# ZenDriver_Mini2.net
KiCad netlist of a schematic drawn in Altium Designer
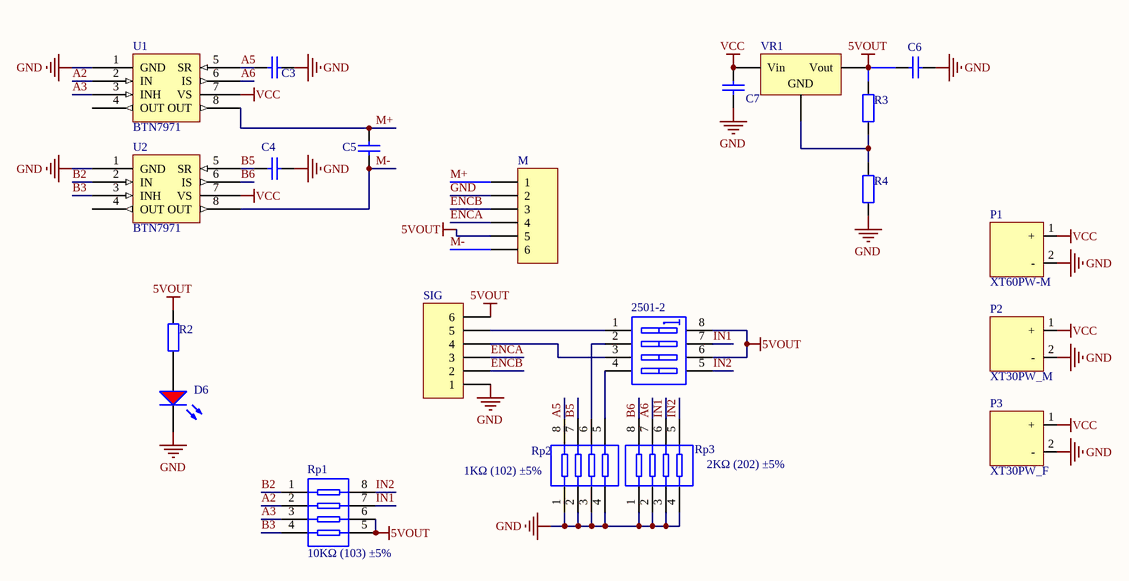
[diagram p0: ZenDriver_Mini2.SchDoc]

(export (version "E")
  (design (tool "Eeschema 10.0.6"))
  (components
    (comp (ref "2501-2")
      (value "2501-2")
      (footprint "*DIP762W50P254L977H451Q8")
      (description "DIP Switch, 4 Position, SPST")
      (fields (field (name "PUBLISHER") "Altium Limited"))
      (libsource (lib "Miscellaneous Devices") (part "SW DIP-4"))
    )
    (comp (ref "C3")
      (value "100nF (104) 10% 50V")
      (footprint "0603_C")
      (description "贴片电容")
      (libsource (lib "Miscellaneous Devices LC") (part "0603 100nF (104) 10% 50V"))
    )
    (comp (ref "C4")
      (value "100nF (104) 10% 50V")
      (footprint "0603_C")
      (description "贴片电容")
      (libsource (lib "Miscellaneous Devices LC") (part "0603 100nF (104) 10% 50V"))
    )
    (comp (ref "C5")
      (value "22pF (220) 5% 50V")
      (footprint "0603_C")
      (description "贴片电容")
      (libsource (lib "Miscellaneous Devices LC") (part "0603 22pF (220) 5% 50V"))
    )
    (comp (ref "C6")
      (value "100nF (104) 10% 50V")
      (footprint "0603_C")
      (description "贴片电容")
      (libsource (lib "Miscellaneous Devices LC") (part "0603 100nF (104) 10% 50V"))
    )
    (comp (ref "C7")
      (value "100nF (104) 10% 50V")
      (footprint "0603_C")
      (description "贴片电容")
      (libsource (lib "Miscellaneous Devices LC") (part "0603 100nF (104) 10% 50V"))
    )
    (comp (ref "D6")
      (value "红灯 0603")
      (footprint "0603_LED_S1")
      (description "发光二极管")
      (libsource (lib "Miscellaneous Devices LC") (part "0603 红灯"))
    )
    (comp (ref "M")
      (value "Header 6H")
      (footprint "HDR1X6H")
      (description "Header, 6-Pin, Right Angle")
      (fields (field (name "PUBLISHER") "Altium Limited"))
      (libsource (lib "Miscellaneous Connectors") (part "Header 6H"))
    )
    (comp (ref "P1")
      (value "XT60PW-M")
      (footprint "XT60PW-M")
      (description "XT60")
      (libsource (lib "Hare_Library") (part "XT60"))
    )
    (comp (ref "P2")
      (value "XT30PW_M")
      (footprint "XT30PW-M")
      (description "XT30")
      (libsource (lib "Hare_Library") (part "XT30"))
    )
    (comp (ref "P3")
      (value "XT30PW_F")
      (footprint "XT30PW-F")
      (description "XT30")
      (libsource (lib "Hare_Library") (part "XT30"))
    )
    (comp (ref "R2")
      (value "4.7k")
      (footprint "0603_R")
      (description "贴片电阻")
      (libsource (lib "Miscellaneous Devices LC") (part "0603 470Ω (4700) 1%"))
    )
    (comp (ref "R3")
      (value "1KΩ (1001) ±1%")
      (footprint "0603_R")
      (description "贴片电阻")
      (libsource (lib "Miscellaneous Devices LC") (part "0603 1KΩ (1001) 1%"))
    )
    (comp (ref "R4")
      (value "3KΩ (3001) ±1%")
      (footprint "0603_R")
      (description "贴片电阻")
      (libsource (lib "Miscellaneous Devices LC") (part "0603 3KΩ (3001) 1%"))
    )
    (comp (ref "Rp1")
      (value "10KΩ (103) ±5%")
      (footprint "0603_Rx4")
      (description "贴片排阻")
      (libsource (lib "Miscellaneous Devices LC") (part "0603*4  10KΩ (103) 5%"))
    )
    (comp (ref "Rp2")
      (value "1KΩ (102) ±5%")
      (footprint "0603_Rx4")
      (description "贴片排阻")
      (libsource (lib "Miscellaneous Devices LC") (part "0603*4  1KΩ (102) 5%"))
    )
    (comp (ref "Rp3")
      (value "2KΩ (202) ±5%")
      (footprint "0603_Rx4")
      (description "贴片排阻")
      (libsource (lib "Miscellaneous Devices LC") (part "0603*4  1KΩ (102) 5%"))
    )
    (comp (ref "SIG")
      (value "Header 6H")
      (footprint "HDR1X6H")
      (description "Header, 6-Pin, Right Angle")
      (fields (field (name "PUBLISHER") "Altium Limited"))
      (libsource (lib "") (part "Header 6H_1"))
    )
    (comp (ref "U1")
      (value "BTN7971")
      (footprint "DPAK127P1615X127-8N")
      (libsource (lib "Sheet2") (part "BTN7971"))
    )
    (comp (ref "U2")
      (value "BTN7971")
      (footprint "DPAK127P1615X127-8N")
      (libsource (lib "Sheet2") (part "BTN7971"))
    )
    (comp (ref "VR1")
      (value "LM317AL-TN3-R")
      (footprint "TO-252-2-180")
      (description "低压差线性稳压(LDO)")
      (libsource (lib "Miscellaneous Devices LC") (part "TO-252-2 LM317AL-TN3-R"))
    )
  )
  (nets
    (net (code "1") (name "/A2") (class "Default")
      (node (ref "Rp1") (pin "2") (pinfunction "2_2") (pintype "passive"))
      (node (ref "U1") (pin "2") (pinfunction "IN_2") (pintype "input"))
    )
    (net (code "2") (name "/A3") (class "Default")
      (node (ref "Rp1") (pin "3") (pinfunction "3_3") (pintype "passive"))
      (node (ref "U1") (pin "3") (pinfunction "INH_3") (pintype "input"))
    )
    (net (code "3") (name "/A5") (class "Default")
      (node (ref "C3") (pin "1") (pinfunction "1_1") (pintype "passive"))
      (node (ref "Rp2") (pin "8") (pinfunction "8_8") (pintype "passive"))
      (node (ref "U1") (pin "5") (pinfunction "SR_5") (pintype "input"))
    )
    (net (code "4") (name "/A6") (class "Default")
      (node (ref "Rp3") (pin "7") (pinfunction "7_7") (pintype "passive"))
      (node (ref "U1") (pin "6") (pinfunction "IS_6") (pintype "output"))
    )
    (net (code "5") (name "/B2") (class "Default")
      (node (ref "Rp1") (pin "1") (pinfunction "1_1") (pintype "passive"))
      (node (ref "U2") (pin "2") (pinfunction "IN_2") (pintype "input"))
    )
    (net (code "6") (name "/B3") (class "Default")
      (node (ref "Rp1") (pin "4") (pinfunction "4_4") (pintype "passive"))
      (node (ref "U2") (pin "3") (pinfunction "INH_3") (pintype "input"))
    )
    (net (code "7") (name "/B5") (class "Default")
      (node (ref "C4") (pin "1") (pinfunction "1_1") (pintype "passive"))
      (node (ref "Rp2") (pin "7") (pinfunction "7_7") (pintype "passive"))
      (node (ref "U2") (pin "5") (pinfunction "SR_5") (pintype "input"))
    )
    (net (code "8") (name "/B6") (class "Default")
      (node (ref "Rp3") (pin "8") (pinfunction "8_8") (pintype "passive"))
      (node (ref "U2") (pin "6") (pinfunction "IS_6") (pintype "output"))
    )
    (net (code "9") (name "/ENCA") (class "Default")
      (node (ref "M") (pin "4") (pinfunction "4_4") (pintype "passive"))
      (node (ref "SIG") (pin "3") (pinfunction "3_3") (pintype "passive"))
    )
    (net (code "10") (name "/ENCB") (class "Default")
      (node (ref "M") (pin "3") (pinfunction "3_3") (pintype "passive"))
      (node (ref "SIG") (pin "2") (pinfunction "2_2") (pintype "passive"))
    )
    (net (code "11") (name "/IN1") (class "Default")
      (node (ref "2501-2") (pin "7") (pinfunction "B2_7") (pintype "passive"))
      (node (ref "Rp1") (pin "7") (pinfunction "7_7") (pintype "passive"))
      (node (ref "Rp3") (pin "6") (pinfunction "6_6") (pintype "passive"))
    )
    (net (code "12") (name "/IN2") (class "Default")
      (node (ref "2501-2") (pin "5") (pinfunction "B4_5") (pintype "passive"))
      (node (ref "Rp1") (pin "8") (pinfunction "8_8") (pintype "passive"))
      (node (ref "Rp3") (pin "5") (pinfunction "5_5") (pintype "passive"))
    )
    (net (code "13") (name "/M+") (class "Default")
      (node (ref "C5") (pin "2") (pinfunction "2_2") (pintype "passive"))
      (node (ref "M") (pin "1") (pinfunction "1_1") (pintype "passive"))
      (node (ref "U1") (pin "8") (pinfunction "OUT_8") (pintype "output"))
    )
    (net (code "14") (name "/M-") (class "Default")
      (node (ref "C5") (pin "1") (pinfunction "1_1") (pintype "passive"))
      (node (ref "M") (pin "6") (pinfunction "6_6") (pintype "passive"))
      (node (ref "U2") (pin "8") (pinfunction "OUT_8") (pintype "output"))
    )
    (net (code "15") (name "5VOUT") (class "Default")
      (node (ref "2501-2") (pin "6") (pinfunction "B3_6") (pintype "passive"))
      (node (ref "2501-2") (pin "8") (pinfunction "B1_8") (pintype "passive"))
      (node (ref "C6") (pin "1") (pinfunction "1_1") (pintype "passive"))
      (node (ref "M") (pin "5") (pinfunction "5_5") (pintype "passive"))
      (node (ref "R2") (pin "2") (pinfunction "2_2") (pintype "passive"))
      (node (ref "R3") (pin "2") (pinfunction "2_2") (pintype "passive"))
      (node (ref "Rp1") (pin "5") (pinfunction "5_5") (pintype "passive"))
      (node (ref "Rp1") (pin "6") (pinfunction "6_6") (pintype "passive"))
      (node (ref "SIG") (pin "6") (pinfunction "6_6") (pintype "passive"))
      (node (ref "VR1") (pin "2") (pinfunction "Vout_2") (pintype "passive"))
    )
    (net (code "16") (name "GND") (class "Default")
      (node (ref "C3") (pin "2") (pinfunction "2_2") (pintype "passive"))
      (node (ref "C4") (pin "2") (pinfunction "2_2") (pintype "passive"))
      (node (ref "C6") (pin "2") (pinfunction "2_2") (pintype "passive"))
      (node (ref "C7") (pin "1") (pinfunction "1_1") (pintype "passive"))
      (node (ref "D6") (pin "K") (pinfunction "K_K") (pintype "passive"))
      (node (ref "M") (pin "2") (pinfunction "2_2") (pintype "passive"))
      (node (ref "P1") (pin "2") (pinfunction "-_2") (pintype "passive"))
      (node (ref "P2") (pin "2") (pinfunction "-_2") (pintype "passive"))
      (node (ref "P3") (pin "2") (pinfunction "-_2") (pintype "passive"))
      (node (ref "R4") (pin "1") (pinfunction "1_1") (pintype "passive"))
      (node (ref "Rp2") (pin "1") (pinfunction "1_1") (pintype "passive"))
      (node (ref "Rp2") (pin "2") (pinfunction "2_2") (pintype "passive"))
      (node (ref "Rp2") (pin "3") (pinfunction "3_3") (pintype "passive"))
      (node (ref "Rp2") (pin "4") (pinfunction "4_4") (pintype "passive"))
      (node (ref "Rp3") (pin "1") (pinfunction "1_1") (pintype "passive"))
      (node (ref "Rp3") (pin "2") (pinfunction "2_2") (pintype "passive"))
      (node (ref "Rp3") (pin "3") (pinfunction "3_3") (pintype "passive"))
      (node (ref "Rp3") (pin "4") (pinfunction "4_4") (pintype "passive"))
      (node (ref "SIG") (pin "1") (pinfunction "1_1") (pintype "passive"))
      (node (ref "U1") (pin "1") (pinfunction "GND_1") (pintype "passive"))
      (node (ref "U2") (pin "1") (pinfunction "GND_1") (pintype "passive"))
    )
    (net (code "17") (name "Net-(2501-2-A1)") (class "Default")
      (node (ref "2501-2") (pin "1") (pinfunction "A1_1") (pintype "passive"))
      (node (ref "SIG") (pin "5") (pinfunction "5_5") (pintype "passive"))
    )
    (net (code "18") (name "Net-(2501-2-A2)") (class "Default")
      (node (ref "2501-2") (pin "2") (pinfunction "A2_2") (pintype "passive"))
      (node (ref "Rp2") (pin "6") (pinfunction "6_6") (pintype "passive"))
    )
    (net (code "19") (name "Net-(2501-2-A3)") (class "Default")
      (node (ref "2501-2") (pin "3") (pinfunction "A3_3") (pintype "passive"))
      (node (ref "SIG") (pin "4") (pinfunction "4_4") (pintype "passive"))
    )
    (net (code "20") (name "Net-(2501-2-A4)") (class "Default")
      (node (ref "2501-2") (pin "4") (pinfunction "A4_4") (pintype "passive"))
      (node (ref "Rp2") (pin "5") (pinfunction "5_5") (pintype "passive"))
    )
    (net (code "21") (name "Net-(D6-PadA)") (class "Default")
      (node (ref "D6") (pin "A") (pinfunction "A_A") (pintype "passive"))
      (node (ref "R2") (pin "1") (pinfunction "1_1") (pintype "passive"))
    )
    (net (code "22") (name "Net-(VR1-GND)") (class "Default")
      (node (ref "R3") (pin "1") (pinfunction "1_1") (pintype "passive"))
      (node (ref "R4") (pin "2") (pinfunction "2_2") (pintype "passive"))
      (node (ref "VR1") (pin "1") (pinfunction "GND_1") (pintype "passive"))
    )
    (net (code "23") (name "VCC") (class "Default")
      (node (ref "C7") (pin "2") (pinfunction "2_2") (pintype "passive"))
      (node (ref "P1") (pin "1") (pinfunction "+_1") (pintype "passive"))
      (node (ref "P2") (pin "1") (pinfunction "+_1") (pintype "passive"))
      (node (ref "P3") (pin "1") (pinfunction "+_1") (pintype "passive"))
      (node (ref "U1") (pin "7") (pinfunction "VS_7") (pintype "passive"))
      (node (ref "U2") (pin "7") (pinfunction "VS_7") (pintype "passive"))
      (node (ref "VR1") (pin "3") (pinfunction "Vin_3") (pintype "passive"))
    )
    (net (code "24") (name "unconnected-(U1-OUT-Pad4)") (class "Default")
      (node (ref "U1") (pin "4") (pinfunction "OUT_4") (pintype "output"))
    )
    (net (code "25") (name "unconnected-(U2-OUT-Pad4)") (class "Default")
      (node (ref "U2") (pin "4") (pinfunction "OUT_4") (pintype "output"))
    )
  )
)
